# FC_nano.net
KiCad netlist of a schematic drawn in EAGLE
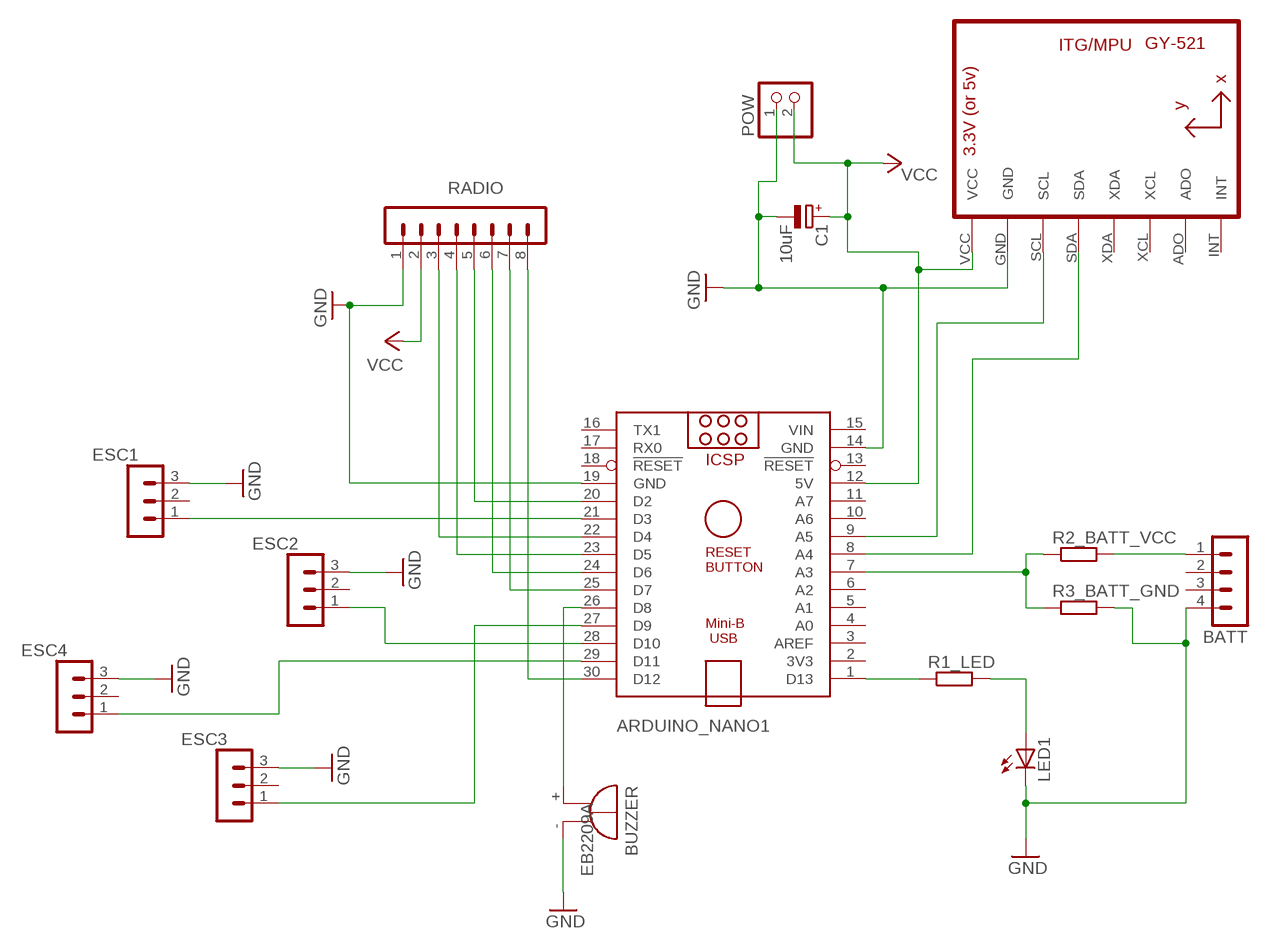
[diagram p0: schematic, sheet 1]

(export (version "E")
  (design (tool "Eeschema 10.0.6"))
  (components
    (comp (ref "ARDUINO_NANO1")
      (value "ARDUINO_NANO")
      (footprint "eagle-import:ARDUINO_NANO")
      (libsource (lib "eagle-import") (part "ARDUINO_NANO"))
    )
    (comp (ref "BATT")
      (value "MA04-1")
      (footprint "eagle-import:MA04-1")
      (libsource (lib "eagle-import") (part "MA04-1"))
    )
    (comp (ref "BUZZER")
      (value "EB2209A")
      (footprint "eagle-import:EB2209A")
      (libsource (lib "eagle-import") (part "EB2209A"))
    )
    (comp (ref "C1")
      (value "10uF")
      (footprint "eagle-import:E2-5")
      (libsource (lib "eagle-import") (part "CPOL-EUE2-5"))
    )
    (comp (ref "ESC1")
      (value "MA03-1")
      (footprint "eagle-import:MA03-1")
      (libsource (lib "eagle-import") (part "MA03-1"))
    )
    (comp (ref "ESC2")
      (value "MA03-1")
      (footprint "eagle-import:MA03-1")
      (libsource (lib "eagle-import") (part "MA03-1"))
    )
    (comp (ref "ESC3")
      (value "MA03-1")
      (footprint "eagle-import:MA03-1")
      (libsource (lib "eagle-import") (part "MA03-1"))
    )
    (comp (ref "ESC4")
      (value "MA03-1")
      (footprint "eagle-import:MA03-1")
      (libsource (lib "eagle-import") (part "MA03-1"))
    )
    (comp (ref "LED1")
      (value "LED3MM")
      (footprint "eagle-import:LED3MM")
      (libsource (lib "eagle-import") (part "LED3MM"))
    )
    (comp (ref "POW")
      (value "PINHD-1X2")
      (footprint "eagle-import:1X02")
      (libsource (lib "eagle-import") (part "PINHD-1X2"))
    )
    (comp (ref "R1_LED")
      (value "R-EU_0204/7")
      (footprint "eagle-import:0204_7")
      (libsource (lib "eagle-import") (part "R-EU_0204/7"))
    )
    (comp (ref "R2_BATT_VCC")
      (value "R-EU_0204/7")
      (footprint "eagle-import:0204_7")
      (libsource (lib "eagle-import") (part "R-EU_0204/7"))
    )
    (comp (ref "R3_BATT_GND")
      (value "R-EU_0204/7")
      (footprint "eagle-import:0204_7")
      (libsource (lib "eagle-import") (part "R-EU_0204/7"))
    )
    (comp (ref "RADIO")
      (value "MA08-1")
      (footprint "eagle-import:MA08-1")
      (libsource (lib "eagle-import") (part "MA08-1"))
    )
    (comp (ref "U1")
      (value "GY-521MPU6050")
      (footprint "eagle-import:GY-521")
      (libsource (lib "eagle-import") (part "GY-521MPU6050"))
    )
  )
  (nets
    (net (code "1") (name "/VIN") (class "Default")
      (node (ref "ARDUINO_NANO1") (pin "15") (pinfunction "VIN_15") (pintype "power_in"))
    )
    (net (code "2") (name "GND") (class "Default")
      (node (ref "ARDUINO_NANO1") (pin "14") (pinfunction "GND_14") (pintype "power_in"))
      (node (ref "ARDUINO_NANO1") (pin "19") (pinfunction "GND_19") (pintype "power_in"))
      (node (ref "BATT") (pin "4") (pinfunction "4_4") (pintype "passive"))
      (node (ref "BUZZER") (pin "-") (pinfunction "-_-") (pintype "passive"))
      (node (ref "C1") (pin "-") (pinfunction "-_-") (pintype "passive"))
      (node (ref "ESC1") (pin "3") (pinfunction "3_3") (pintype "passive"))
      (node (ref "ESC2") (pin "3") (pinfunction "3_3") (pintype "passive"))
      (node (ref "ESC3") (pin "3") (pinfunction "3_3") (pintype "passive"))
      (node (ref "ESC4") (pin "3") (pinfunction "3_3") (pintype "passive"))
      (node (ref "LED1") (pin "K") (pinfunction "C_K") (pintype "passive"))
      (node (ref "POW") (pin "1") (pinfunction "1_1") (pintype "passive"))
      (node (ref "R3_BATT_GND") (pin "2") (pinfunction "2_2") (pintype "passive"))
      (node (ref "RADIO") (pin "1") (pinfunction "1_1") (pintype "passive"))
      (node (ref "U1") (pin "GND") (pinfunction "GND_GND") (pintype "bidirectional"))
    )
    (net (code "3") (name "Net-(ARDUINO_NANO1-A3)") (class "Default")
      (node (ref "ARDUINO_NANO1") (pin "7") (pinfunction "A3_7") (pintype "bidirectional"))
      (node (ref "R2_BATT_VCC") (pin "1") (pinfunction "1_1") (pintype "passive"))
      (node (ref "R3_BATT_GND") (pin "1") (pinfunction "1_1") (pintype "passive"))
    )
    (net (code "4") (name "Net-(ARDUINO_NANO1-A4)") (class "Default")
      (node (ref "ARDUINO_NANO1") (pin "8") (pinfunction "A4_8") (pintype "bidirectional"))
      (node (ref "U1") (pin "SDA") (pinfunction "SDA_SDA") (pintype "bidirectional"))
    )
    (net (code "5") (name "Net-(ARDUINO_NANO1-A5)") (class "Default")
      (node (ref "ARDUINO_NANO1") (pin "9") (pinfunction "A5_9") (pintype "bidirectional"))
      (node (ref "U1") (pin "SCL") (pinfunction "SCL_SCL") (pintype "bidirectional"))
    )
    (net (code "6") (name "Net-(ARDUINO_NANO1-D2)") (class "Default")
      (node (ref "ARDUINO_NANO1") (pin "20") (pinfunction "D2_20") (pintype "bidirectional"))
      (node (ref "RADIO") (pin "5") (pinfunction "5_5") (pintype "passive"))
    )
    (net (code "7") (name "Net-(ARDUINO_NANO1-D3)") (class "Default")
      (node (ref "ARDUINO_NANO1") (pin "21") (pinfunction "D3_21") (pintype "bidirectional"))
      (node (ref "ESC1") (pin "1") (pinfunction "1_1") (pintype "passive"))
    )
    (net (code "8") (name "Net-(ARDUINO_NANO1-D4)") (class "Default")
      (node (ref "ARDUINO_NANO1") (pin "22") (pinfunction "D4_22") (pintype "bidirectional"))
      (node (ref "RADIO") (pin "3") (pinfunction "3_3") (pintype "passive"))
    )
    (net (code "9") (name "Net-(ARDUINO_NANO1-D5)") (class "Default")
      (node (ref "ARDUINO_NANO1") (pin "23") (pinfunction "D5_23") (pintype "bidirectional"))
      (node (ref "RADIO") (pin "4") (pinfunction "4_4") (pintype "passive"))
    )
    (net (code "10") (name "Net-(ARDUINO_NANO1-D6)") (class "Default")
      (node (ref "ARDUINO_NANO1") (pin "24") (pinfunction "D6_24") (pintype "bidirectional"))
      (node (ref "RADIO") (pin "6") (pinfunction "6_6") (pintype "passive"))
    )
    (net (code "11") (name "Net-(ARDUINO_NANO1-D7)") (class "Default")
      (node (ref "ARDUINO_NANO1") (pin "25") (pinfunction "D7_25") (pintype "bidirectional"))
      (node (ref "RADIO") (pin "7") (pinfunction "7_7") (pintype "passive"))
    )
    (net (code "12") (name "Net-(ARDUINO_NANO1-D8)") (class "Default")
      (node (ref "ARDUINO_NANO1") (pin "26") (pinfunction "D8_26") (pintype "bidirectional"))
      (node (ref "BUZZER") (pin "+") (pinfunction "+_+") (pintype "passive"))
    )
    (net (code "13") (name "Net-(ARDUINO_NANO1-D9)") (class "Default")
      (node (ref "ARDUINO_NANO1") (pin "27") (pinfunction "D9_27") (pintype "bidirectional"))
      (node (ref "ESC3") (pin "1") (pinfunction "1_1") (pintype "passive"))
    )
    (net (code "14") (name "Net-(ARDUINO_NANO1-D10)") (class "Default")
      (node (ref "ARDUINO_NANO1") (pin "28") (pinfunction "D10_28") (pintype "bidirectional"))
      (node (ref "ESC2") (pin "1") (pinfunction "1_1") (pintype "passive"))
    )
    (net (code "15") (name "Net-(ARDUINO_NANO1-D11)") (class "Default")
      (node (ref "ARDUINO_NANO1") (pin "29") (pinfunction "D11_29") (pintype "bidirectional"))
      (node (ref "ESC4") (pin "1") (pinfunction "1_1") (pintype "passive"))
    )
    (net (code "16") (name "Net-(ARDUINO_NANO1-D12)") (class "Default")
      (node (ref "ARDUINO_NANO1") (pin "30") (pinfunction "D12_30") (pintype "bidirectional"))
      (node (ref "RADIO") (pin "8") (pinfunction "8_8") (pintype "passive"))
    )
    (net (code "17") (name "Net-(ARDUINO_NANO1-D13)") (class "Default")
      (node (ref "ARDUINO_NANO1") (pin "1") (pinfunction "D13_1") (pintype "bidirectional"))
      (node (ref "R1_LED") (pin "1") (pinfunction "1_1") (pintype "passive"))
    )
    (net (code "18") (name "Net-(BATT-Pad1)") (class "Default")
      (node (ref "BATT") (pin "1") (pinfunction "1_1") (pintype "passive"))
      (node (ref "R2_BATT_VCC") (pin "2") (pinfunction "2_2") (pintype "passive"))
    )
    (net (code "19") (name "Net-(LED1-PadA)") (class "Default")
      (node (ref "LED1") (pin "A") (pinfunction "A_A") (pintype "passive"))
      (node (ref "R1_LED") (pin "2") (pinfunction "2_2") (pintype "passive"))
    )
    (net (code "20") (name "VCC") (class "Default")
      (node (ref "ARDUINO_NANO1") (pin "12") (pinfunction "5V_12") (pintype "power_in"))
      (node (ref "C1") (pin "+") (pinfunction "+_+") (pintype "passive"))
      (node (ref "POW") (pin "2") (pinfunction "2_2") (pintype "passive"))
      (node (ref "RADIO") (pin "2") (pinfunction "2_2") (pintype "passive"))
      (node (ref "U1") (pin "VCC") (pinfunction "VCC_VCC") (pintype "bidirectional"))
    )
    (net (code "21") (name "unconnected-(ARDUINO_NANO1-3V3-Pad2)") (class "Default")
      (node (ref "ARDUINO_NANO1") (pin "2") (pinfunction "3V3_2") (pintype "output"))
    )
    (net (code "22") (name "unconnected-(ARDUINO_NANO1-A0-Pad4)") (class "Default")
      (node (ref "ARDUINO_NANO1") (pin "4") (pinfunction "A0_4") (pintype "bidirectional"))
    )
    (net (code "23") (name "unconnected-(ARDUINO_NANO1-A1-Pad5)") (class "Default")
      (node (ref "ARDUINO_NANO1") (pin "5") (pinfunction "A1_5") (pintype "bidirectional"))
    )
    (net (code "24") (name "unconnected-(ARDUINO_NANO1-A2-Pad6)") (class "Default")
      (node (ref "ARDUINO_NANO1") (pin "6") (pinfunction "A2_6") (pintype "bidirectional"))
    )
    (net (code "25") (name "unconnected-(ARDUINO_NANO1-A6-Pad10)") (class "Default")
      (node (ref "ARDUINO_NANO1") (pin "10") (pinfunction "A6_10") (pintype "bidirectional"))
    )
    (net (code "26") (name "unconnected-(ARDUINO_NANO1-A7-Pad11)") (class "Default")
      (node (ref "ARDUINO_NANO1") (pin "11") (pinfunction "A7_11") (pintype "bidirectional"))
    )
    (net (code "27") (name "unconnected-(ARDUINO_NANO1-AREF-Pad3)") (class "Default")
      (node (ref "ARDUINO_NANO1") (pin "3") (pinfunction "AREF_3") (pintype "input"))
    )
    (net (code "28") (name "unconnected-(ARDUINO_NANO1-RX0-Pad17)") (class "Default")
      (node (ref "ARDUINO_NANO1") (pin "17") (pinfunction "RX0_17") (pintype "bidirectional"))
    )
    (net (code "29") (name "unconnected-(ARDUINO_NANO1-TX1-Pad16)") (class "Default")
      (node (ref "ARDUINO_NANO1") (pin "16") (pinfunction "TX1_16") (pintype "bidirectional"))
    )
    (net (code "30") (name "unconnected-(ARDUINO_NANO1-~{RESET}-Pad13)") (class "Default")
      (node (ref "ARDUINO_NANO1") (pin "13") (pinfunction "~{RESET}_13") (pintype "input"))
    )
    (net (code "31") (name "unconnected-(ARDUINO_NANO1-~{RESET}-Pad18)") (class "Default")
      (node (ref "ARDUINO_NANO1") (pin "18") (pinfunction "~{RESET}_18") (pintype "input"))
    )
    (net (code "32") (name "unconnected-(BATT-Pad2)") (class "Default")
      (node (ref "BATT") (pin "2") (pinfunction "2_2") (pintype "passive"))
    )
    (net (code "33") (name "unconnected-(BATT-Pad3)") (class "Default")
      (node (ref "BATT") (pin "3") (pinfunction "3_3") (pintype "passive"))
    )
    (net (code "34") (name "unconnected-(ESC1-Pad2)") (class "Default")
      (node (ref "ESC1") (pin "2") (pinfunction "2_2") (pintype "passive"))
    )
    (net (code "35") (name "unconnected-(ESC2-Pad2)") (class "Default")
      (node (ref "ESC2") (pin "2") (pinfunction "2_2") (pintype "passive"))
    )
    (net (code "36") (name "unconnected-(ESC3-Pad2)") (class "Default")
      (node (ref "ESC3") (pin "2") (pinfunction "2_2") (pintype "passive"))
    )
    (net (code "37") (name "unconnected-(ESC4-Pad2)") (class "Default")
      (node (ref "ESC4") (pin "2") (pinfunction "2_2") (pintype "passive"))
    )
    (net (code "38") (name "unconnected-(U1-PadADO)") (class "Default")
      (node (ref "U1") (pin "ADO") (pinfunction "ADO_ADO") (pintype "bidirectional"))
    )
    (net (code "39") (name "unconnected-(U1-PadINT)") (class "Default")
      (node (ref "U1") (pin "INT") (pinfunction "INT_INT") (pintype "bidirectional"))
    )
    (net (code "40") (name "unconnected-(U1-PadXCL)") (class "Default")
      (node (ref "U1") (pin "XCL") (pinfunction "XCL_XCL") (pintype "bidirectional"))
    )
    (net (code "41") (name "unconnected-(U1-PadXDA)") (class "Default")
      (node (ref "U1") (pin "XDA") (pinfunction "XDA_XDA") (pintype "bidirectional"))
    )
  )
)
